# controller.net
KiCad netlist of a schematic drawn in EAGLE
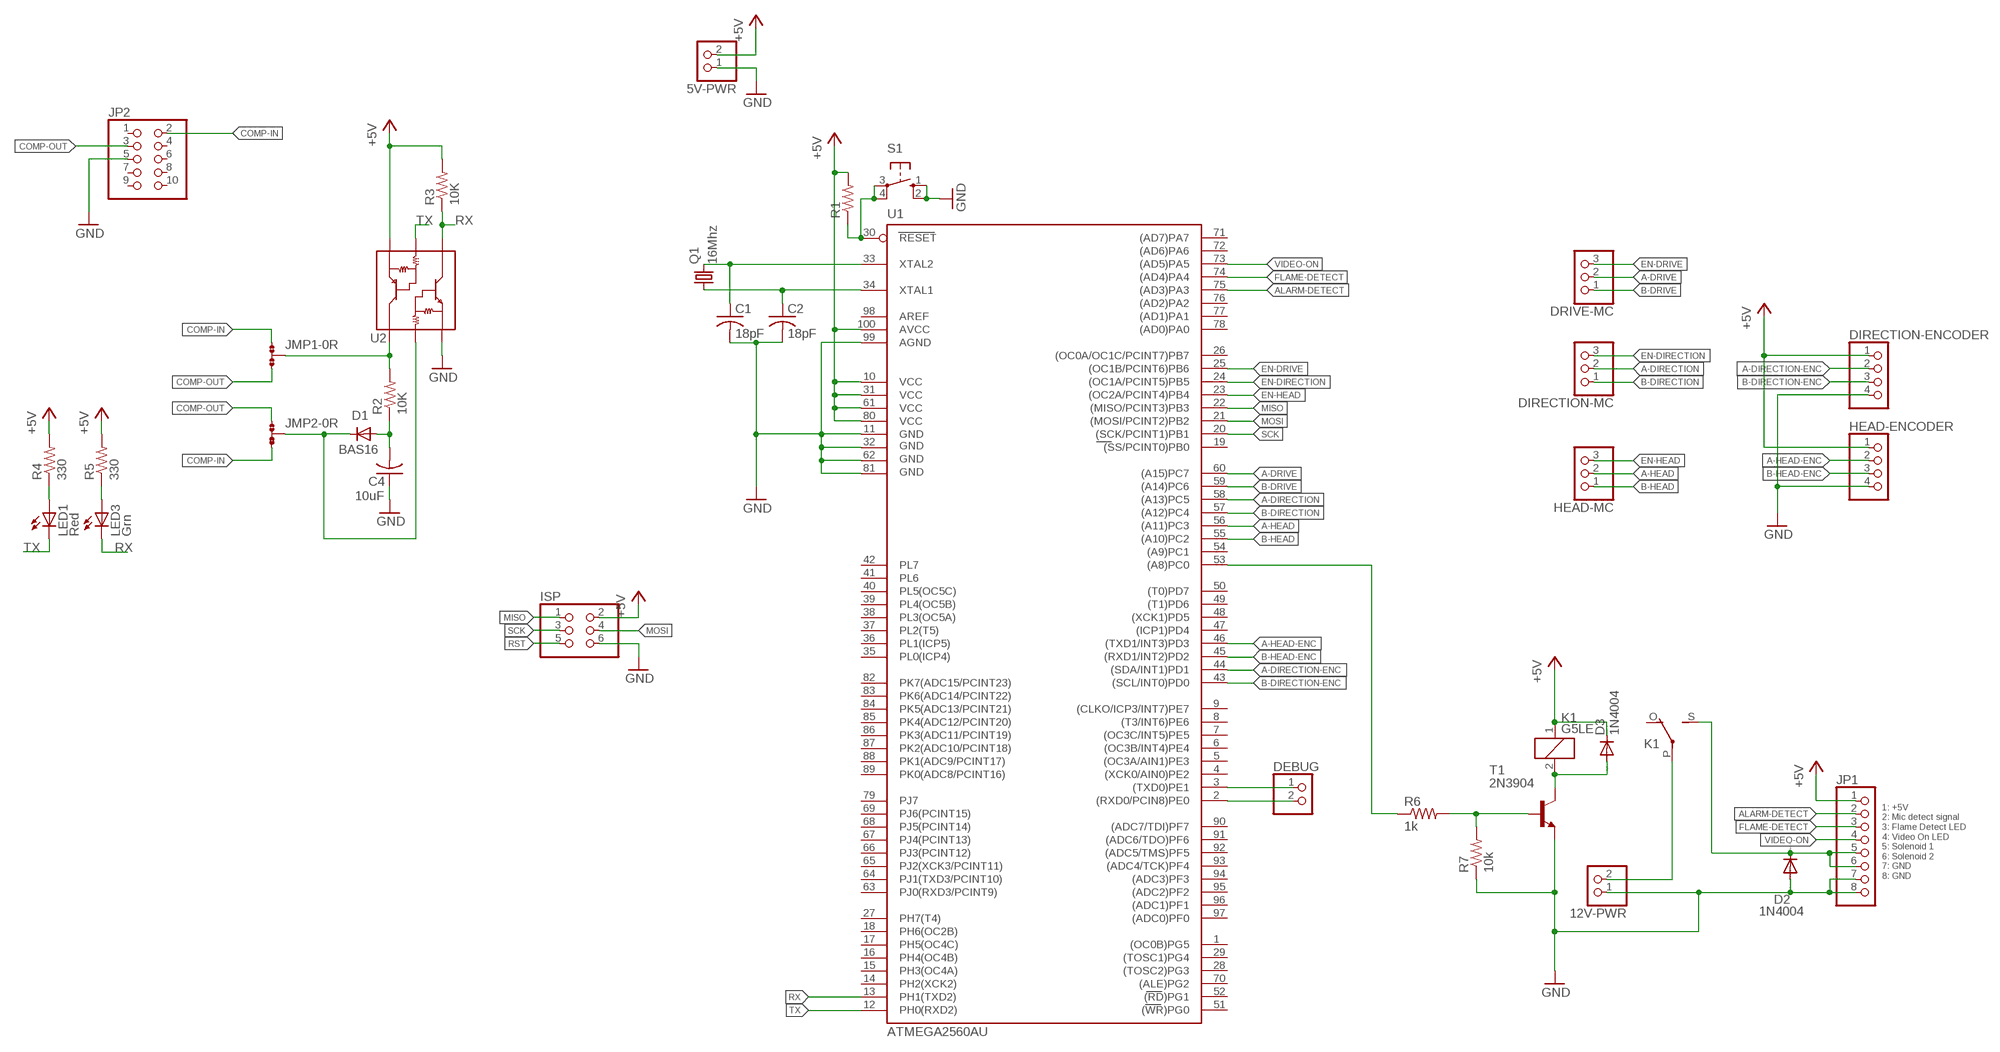
[diagram p0: schematic, sheet 1]

(export (version "E")
  (design (tool "Eeschema 10.0.6"))
  (components
    (comp (ref "5V-PWR")
      (value "PINHD-1X2")
      (footprint "eagle-import:1X02")
      (libsource (lib "eagle-import") (part "PINHD-1X2"))
    )
    (comp (ref "12V-PWR")
      (value "PINHD-1X2")
      (footprint "eagle-import:1X02")
      (libsource (lib "eagle-import") (part "PINHD-1X2"))
    )
    (comp (ref "C1")
      (value "18pF")
      (footprint "eagle-import:C0402K")
      (libsource (lib "eagle-import") (part "C-USC0402K"))
    )
    (comp (ref "C2")
      (value "18pF")
      (footprint "eagle-import:C0402K")
      (libsource (lib "eagle-import") (part "C-USC0402K"))
    )
    (comp (ref "C4")
      (value "10uF")
      (footprint "eagle-import:C0805")
      (libsource (lib "eagle-import") (part "resistor_C-USC0805"))
    )
    (comp (ref "D1")
      (value "BAS16")
      (footprint "eagle-import:SOD-323")
      (libsource (lib "eagle-import") (part "DIODESOD"))
    )
    (comp (ref "D2")
      (value "1N4004")
      (footprint "eagle-import:DO41-10")
      (libsource (lib "eagle-import") (part "1N4004"))
    )
    (comp (ref "D3")
      (value "1N4004")
      (footprint "eagle-import:DO41-10")
      (libsource (lib "eagle-import") (part "1N4004"))
    )
    (comp (ref "DEBUG")
      (value "PINHD-1X2")
      (footprint "eagle-import:1X02")
      (libsource (lib "eagle-import") (part "PINHD-1X2"))
    )
    (comp (ref "DIRECTION-ENCODER")
      (value "PINHD-1X4")
      (footprint "eagle-import:1X04")
      (libsource (lib "eagle-import") (part "PINHD-1X4"))
    )
    (comp (ref "DIRECTION-MC")
      (value "PINHD-1X3")
      (footprint "eagle-import:1X03")
      (libsource (lib "eagle-import") (part "PINHD-1X3"))
    )
    (comp (ref "DRIVE-MC")
      (value "PINHD-1X3")
      (footprint "eagle-import:1X03")
      (libsource (lib "eagle-import") (part "PINHD-1X3"))
    )
    (comp (ref "HEAD-ENCODER")
      (value "PINHD-1X4")
      (footprint "eagle-import:1X04")
      (libsource (lib "eagle-import") (part "PINHD-1X4"))
    )
    (comp (ref "HEAD-MC")
      (value "PINHD-1X3")
      (footprint "eagle-import:1X03")
      (libsource (lib "eagle-import") (part "PINHD-1X3"))
    )
    (comp (ref "ISP")
      (value "PINHD-2X3")
      (footprint "eagle-import:2X03")
      (libsource (lib "eagle-import") (part "PINHD-2X3"))
    )
    (comp (ref "JMP1")
      (value "0R-JUMPA")
      (footprint "eagle-import:A0R-JMP")
      (libsource (lib "eagle-import") (part "0R-JUMPA"))
    )
    (comp (ref "JMP2")
      (value "0R-JUMPA")
      (footprint "eagle-import:A0R-JMP")
      (libsource (lib "eagle-import") (part "0R-JUMPA"))
    )
    (comp (ref "JP1")
      (value "PINHD-1X8")
      (footprint "eagle-import:1X08")
      (libsource (lib "eagle-import") (part "PINHD-1X8"))
    )
    (comp (ref "JP2")
      (value "PINHD-2X5")
      (footprint "eagle-import:2X05")
      (libsource (lib "eagle-import") (part "PINHD-2X5"))
    )
    (comp (ref "K1")
      (value "G5LE")
      (footprint "eagle-import:G5LE")
      (libsource (lib "eagle-import") (part "G5LE"))
    )
    (comp (ref "LED1")
      (value "Red")
      (footprint "eagle-import:LED-1206")
      (libsource (lib "eagle-import") (part "LED1206"))
    )
    (comp (ref "LED3")
      (value "Grn")
      (footprint "eagle-import:LED-1206")
      (libsource (lib "eagle-import") (part "LED1206"))
    )
    (comp (ref "Q1")
      (value "16Mhz")
      (footprint "eagle-import:HC49_S")
      (libsource (lib "eagle-import") (part "CRYSTALHC49S"))
    )
    (comp (ref "R1")
      (value "R-US_M0805")
      (footprint "eagle-import:M0805")
      (libsource (lib "eagle-import") (part "R-US_M0805"))
    )
    (comp (ref "R2")
      (value "10K")
      (footprint "eagle-import:R0805")
      (libsource (lib "eagle-import") (part "resistor_R-US_R0805"))
    )
    (comp (ref "R3")
      (value "10K")
      (footprint "eagle-import:R0805")
      (libsource (lib "eagle-import") (part "resistor_R-US_R0805"))
    )
    (comp (ref "R4")
      (value "330")
      (footprint "eagle-import:R0805")
      (libsource (lib "eagle-import") (part "resistor_R-US_R0805"))
    )
    (comp (ref "R5")
      (value "330")
      (footprint "eagle-import:R0805")
      (libsource (lib "eagle-import") (part "resistor_R-US_R0805"))
    )
    (comp (ref "R6")
      (value "1k")
      (footprint "eagle-import:R0805")
      (libsource (lib "eagle-import") (part "R-US_R0805"))
    )
    (comp (ref "R7")
      (value "10k")
      (footprint "eagle-import:R0805")
      (libsource (lib "eagle-import") (part "R-US_R0805"))
    )
    (comp (ref "S1")
      (value "10-XX")
      (footprint "eagle-import:B3F-10XX")
      (fields (field (name "MPN") "B3F-1000"))
      (libsource (lib "eagle-import") (part "10-XX"))
    )
    (comp (ref "T1")
      (value "2N3904")
      (footprint "eagle-import:TO92")
      (libsource (lib "eagle-import") (part "2N3904"))
    )
    (comp (ref "U1")
      (value "ATMEGA2560AU")
      (footprint "eagle-import:TQFP100")
      (libsource (lib "eagle-import") (part "ATMEGA2560AU"))
    )
    (comp (ref "U2")
      (value "XN04312")
      (footprint "eagle-import:SOT23-6")
      (libsource (lib "eagle-import") (part "XN04312SOT"))
    )
  )
  (nets
    (net (code "1") (name "+5V") (class "Default")
      (node (ref "5V-PWR") (pin "2") (pinfunction "2_2") (pintype "passive"))
      (node (ref "D3") (pin "C") (pinfunction "C_C") (pintype "passive"))
      (node (ref "DIRECTION-ENCODER") (pin "1") (pinfunction "1_1") (pintype "passive"))
      (node (ref "HEAD-ENCODER") (pin "1") (pinfunction "1_1") (pintype "passive"))
      (node (ref "ISP") (pin "2") (pinfunction "2_2") (pintype "passive"))
      (node (ref "JP1") (pin "1") (pinfunction "1_1") (pintype "passive"))
      (node (ref "K1") (pin "1") (pinfunction "1_1") (pintype "passive"))
      (node (ref "R1") (pin "2") (pinfunction "2_2") (pintype "passive"))
      (node (ref "R3") (pin "2") (pinfunction "2_2") (pintype "passive"))
      (node (ref "R4") (pin "2") (pinfunction "2_2") (pintype "passive"))
      (node (ref "R5") (pin "2") (pinfunction "2_2") (pintype "passive"))
      (node (ref "U1") (pin "10") (pinfunction "VCC_10") (pintype "power_in"))
      (node (ref "U1") (pin "100") (pinfunction "AVCC_100") (pintype "power_in"))
      (node (ref "U1") (pin "31") (pinfunction "VCC1_31") (pintype "power_in"))
      (node (ref "U1") (pin "61") (pinfunction "VCC2_61") (pintype "power_in"))
      (node (ref "U1") (pin "80") (pinfunction "VCC3_80") (pintype "power_in"))
      (node (ref "U2") (pin "3") (pinfunction "E2_3") (pintype "bidirectional"))
    )
    (net (code "2") (name "A-DIRECTION") (class "Default")
      (node (ref "DIRECTION-MC") (pin "2") (pinfunction "2_2") (pintype "passive"))
      (node (ref "U1") (pin "58") (pinfunction "(A13)PC5_58") (pintype "bidirectional"))
    )
    (net (code "3") (name "A-DIRECTION-ENC") (class "Default")
      (node (ref "DIRECTION-ENCODER") (pin "2") (pinfunction "2_2") (pintype "passive"))
      (node (ref "U1") (pin "44") (pinfunction "(SDA/INT1)PD1_44") (pintype "bidirectional"))
    )
    (net (code "4") (name "A-DRIVE") (class "Default")
      (node (ref "DRIVE-MC") (pin "2") (pinfunction "2_2") (pintype "passive"))
      (node (ref "U1") (pin "60") (pinfunction "(A15)PC7_60") (pintype "bidirectional"))
    )
    (net (code "5") (name "A-HEAD") (class "Default")
      (node (ref "HEAD-MC") (pin "2") (pinfunction "2_2") (pintype "passive"))
      (node (ref "U1") (pin "56") (pinfunction "(A11)PC3_56") (pintype "bidirectional"))
    )
    (net (code "6") (name "A-HEAD-ENC") (class "Default")
      (node (ref "HEAD-ENCODER") (pin "2") (pinfunction "2_2") (pintype "passive"))
      (node (ref "U1") (pin "46") (pinfunction "(TXD1/INT3)PD3_46") (pintype "bidirectional"))
    )
    (net (code "7") (name "ALARM-DETECT") (class "Default")
      (node (ref "JP1") (pin "2") (pinfunction "2_2") (pintype "passive"))
      (node (ref "U1") (pin "75") (pinfunction "(AD3)PA3_75") (pintype "bidirectional"))
    )
    (net (code "8") (name "B-DIRECTION") (class "Default")
      (node (ref "DIRECTION-MC") (pin "1") (pinfunction "1_1") (pintype "passive"))
      (node (ref "U1") (pin "57") (pinfunction "(A12)PC4_57") (pintype "bidirectional"))
    )
    (net (code "9") (name "B-DIRECTION-ENC") (class "Default")
      (node (ref "DIRECTION-ENCODER") (pin "3") (pinfunction "3_3") (pintype "passive"))
      (node (ref "U1") (pin "43") (pinfunction "(SCL/INT0)PD0_43") (pintype "bidirectional"))
    )
    (net (code "10") (name "B-DRIVE") (class "Default")
      (node (ref "DRIVE-MC") (pin "1") (pinfunction "1_1") (pintype "passive"))
      (node (ref "U1") (pin "59") (pinfunction "(A14)PC6_59") (pintype "bidirectional"))
    )
    (net (code "11") (name "B-HEAD") (class "Default")
      (node (ref "HEAD-MC") (pin "1") (pinfunction "1_1") (pintype "passive"))
      (node (ref "U1") (pin "55") (pinfunction "(A10)PC2_55") (pintype "bidirectional"))
    )
    (net (code "12") (name "B-HEAD-ENC") (class "Default")
      (node (ref "HEAD-ENCODER") (pin "3") (pinfunction "3_3") (pintype "passive"))
      (node (ref "U1") (pin "45") (pinfunction "(RXD1/INT2)PD2_45") (pintype "bidirectional"))
    )
    (net (code "13") (name "COMP-IN") (class "Default")
      (node (ref "JMP1") (pin "1") (pinfunction "1_1") (pintype "passive"))
      (node (ref "JMP2") (pin "3") (pinfunction "3_3") (pintype "passive"))
      (node (ref "JP2") (pin "2") (pinfunction "2_2") (pintype "passive"))
    )
    (net (code "14") (name "COMP-OUT") (class "Default")
      (node (ref "JMP1") (pin "3") (pinfunction "3_3") (pintype "passive"))
      (node (ref "JMP2") (pin "1") (pinfunction "1_1") (pintype "passive"))
      (node (ref "JP2") (pin "3") (pinfunction "3_3") (pintype "passive"))
    )
    (net (code "15") (name "EN-DIRECTION") (class "Default")
      (node (ref "DIRECTION-MC") (pin "3") (pinfunction "3_3") (pintype "passive"))
      (node (ref "U1") (pin "24") (pinfunction "(OC1A/PCINT5)PB5_24") (pintype "bidirectional"))
    )
    (net (code "16") (name "EN-DRIVE") (class "Default")
      (node (ref "DRIVE-MC") (pin "3") (pinfunction "3_3") (pintype "passive"))
      (node (ref "U1") (pin "25") (pinfunction "(OC1B/PCINT6)PB6_25") (pintype "bidirectional"))
    )
    (net (code "17") (name "EN-HEAD") (class "Default")
      (node (ref "HEAD-MC") (pin "3") (pinfunction "3_3") (pintype "passive"))
      (node (ref "U1") (pin "23") (pinfunction "(OC2A/PCINT4)PB4_23") (pintype "bidirectional"))
    )
    (net (code "18") (name "FLAME-DETECT") (class "Default")
      (node (ref "JP1") (pin "3") (pinfunction "3_3") (pintype "passive"))
      (node (ref "U1") (pin "74") (pinfunction "(AD4)PA4_74") (pintype "bidirectional"))
    )
    (net (code "19") (name "GND") (class "Default")
      (node (ref "12V-PWR") (pin "1") (pinfunction "1_1") (pintype "passive"))
      (node (ref "5V-PWR") (pin "1") (pinfunction "1_1") (pintype "passive"))
      (node (ref "C1") (pin "2") (pinfunction "2_2") (pintype "passive"))
      (node (ref "C2") (pin "2") (pinfunction "2_2") (pintype "passive"))
      (node (ref "C4") (pin "1") (pinfunction "1_1") (pintype "passive"))
      (node (ref "D2") (pin "A") (pinfunction "A_A") (pintype "passive"))
      (node (ref "DIRECTION-ENCODER") (pin "4") (pinfunction "4_4") (pintype "passive"))
      (node (ref "HEAD-ENCODER") (pin "4") (pinfunction "4_4") (pintype "passive"))
      (node (ref "ISP") (pin "6") (pinfunction "6_6") (pintype "passive"))
      (node (ref "JP1") (pin "7") (pinfunction "7_7") (pintype "passive"))
      (node (ref "JP1") (pin "8") (pinfunction "8_8") (pintype "passive"))
      (node (ref "JP2") (pin "5") (pinfunction "5_5") (pintype "passive"))
      (node (ref "R7") (pin "1") (pinfunction "1_1") (pintype "passive"))
      (node (ref "S1") (pin "1") (pinfunction "S_1") (pintype "passive"))
      (node (ref "S1") (pin "2") (pinfunction "S1_2") (pintype "passive"))
      (node (ref "T1") (pin "3") (pinfunction "E_3") (pintype "passive"))
      (node (ref "U1") (pin "11") (pinfunction "GND_11") (pintype "power_in"))
      (node (ref "U1") (pin "32") (pinfunction "GND1_32") (pintype "power_in"))
      (node (ref "U1") (pin "62") (pinfunction "GND2_62") (pintype "power_in"))
      (node (ref "U1") (pin "81") (pinfunction "GND3_81") (pintype "power_in"))
      (node (ref "U1") (pin "99") (pinfunction "AGND_99") (pintype "power_in"))
      (node (ref "U2") (pin "6") (pinfunction "E1_6") (pintype "bidirectional"))
    )
    (net (code "20") (name "MISO") (class "Default")
      (node (ref "ISP") (pin "1") (pinfunction "1_1") (pintype "passive"))
      (node (ref "U1") (pin "22") (pinfunction "(MISO/PCINT3)PB3_22") (pintype "bidirectional"))
    )
    (net (code "21") (name "MOSI") (class "Default")
      (node (ref "ISP") (pin "4") (pinfunction "4_4") (pintype "passive"))
      (node (ref "U1") (pin "21") (pinfunction "(MOSI/PCINT2)PB2_21") (pintype "bidirectional"))
    )
    (net (code "22") (name "Net-(12V-PWR-Pad2)") (class "Default")
      (node (ref "12V-PWR") (pin "2") (pinfunction "2_2") (pintype "passive"))
      (node (ref "K1") (pin "P") (pinfunction "P_P") (pintype "passive"))
    )
    (net (code "23") (name "Net-(D1-A)") (class "Default")
      (node (ref "C4") (pin "2") (pinfunction "2_2") (pintype "passive"))
      (node (ref "D1") (pin "2") (pinfunction "A_2") (pintype "passive"))
      (node (ref "R2") (pin "1") (pinfunction "1_1") (pintype "passive"))
    )
    (net (code "24") (name "Net-(D1-C)") (class "Default")
      (node (ref "D1") (pin "1") (pinfunction "C_1") (pintype "passive"))
      (node (ref "JMP2") (pin "2") (pinfunction "2_2") (pintype "passive"))
      (node (ref "U2") (pin "5") (pinfunction "B1_5") (pintype "bidirectional"))
    )
    (net (code "25") (name "Net-(D2-PadC)") (class "Default")
      (node (ref "D2") (pin "C") (pinfunction "C_C") (pintype "passive"))
      (node (ref "JP1") (pin "5") (pinfunction "5_5") (pintype "passive"))
      (node (ref "JP1") (pin "6") (pinfunction "6_6") (pintype "passive"))
      (node (ref "K1") (pin "S") (pinfunction "S_S") (pintype "passive"))
    )
    (net (code "26") (name "Net-(LED1-PadA)") (class "Default")
      (node (ref "LED1") (pin "A") (pinfunction "A_A") (pintype "passive"))
      (node (ref "R4") (pin "1") (pinfunction "1_1") (pintype "passive"))
    )
    (net (code "27") (name "Net-(LED3-PadA)") (class "Default")
      (node (ref "LED3") (pin "A") (pinfunction "A_A") (pintype "passive"))
      (node (ref "R5") (pin "1") (pinfunction "1_1") (pintype "passive"))
    )
    (net (code "28") (name "Net-(T1-B)") (class "Default")
      (node (ref "R6") (pin "2") (pinfunction "2_2") (pintype "passive"))
      (node (ref "R7") (pin "2") (pinfunction "2_2") (pintype "passive"))
      (node (ref "T1") (pin "2") (pinfunction "B_2") (pintype "passive"))
    )
    (net (code "29") (name "Net-(T1-C)") (class "Default")
      (node (ref "D3") (pin "A") (pinfunction "A_A") (pintype "passive"))
      (node (ref "K1") (pin "2") (pinfunction "2_2") (pintype "passive"))
      (node (ref "T1") (pin "1") (pinfunction "C_1") (pintype "passive"))
    )
    (net (code "30") (name "Net-(U1-(A8)PC0)") (class "Default")
      (node (ref "R6") (pin "1") (pinfunction "1_1") (pintype "passive"))
      (node (ref "U1") (pin "53") (pinfunction "(A8)PC0_53") (pintype "bidirectional"))
    )
    (net (code "31") (name "Net-(U1-(RXD0{slash}PCIN8)PE0)") (class "Default")
      (node (ref "DEBUG") (pin "2") (pinfunction "2_2") (pintype "passive"))
      (node (ref "U1") (pin "2") (pinfunction "(RXD0/PCIN8)PE0_2") (pintype "bidirectional"))
    )
    (net (code "32") (name "Net-(U1-(TXD0)PE1)") (class "Default")
      (node (ref "DEBUG") (pin "1") (pinfunction "1_1") (pintype "passive"))
      (node (ref "U1") (pin "3") (pinfunction "(TXD0)PE1_3") (pintype "bidirectional"))
    )
    (net (code "33") (name "Net-(U1-XTAL1)") (class "Default")
      (node (ref "C2") (pin "1") (pinfunction "1_1") (pintype "passive"))
      (node (ref "Q1") (pin "1") (pinfunction "1_1") (pintype "passive"))
      (node (ref "U1") (pin "34") (pinfunction "XTAL1_34") (pintype "input"))
    )
    (net (code "34") (name "Net-(U1-XTAL2)") (class "Default")
      (node (ref "C1") (pin "1") (pinfunction "1_1") (pintype "passive"))
      (node (ref "Q1") (pin "2") (pinfunction "2_2") (pintype "passive"))
      (node (ref "U1") (pin "33") (pinfunction "XTAL2_33") (pintype "output"))
    )
    (net (code "35") (name "Net-(U2-C2)") (class "Default")
      (node (ref "JMP1") (pin "2") (pinfunction "2_2") (pintype "passive"))
      (node (ref "R2") (pin "2") (pinfunction "2_2") (pintype "passive"))
      (node (ref "U2") (pin "4") (pinfunction "C2_4") (pintype "bidirectional"))
    )
    (net (code "36") (name "RST") (class "Default")
      (node (ref "ISP") (pin "5") (pinfunction "5_5") (pintype "passive"))
      (node (ref "R1") (pin "1") (pinfunction "1_1") (pintype "passive"))
      (node (ref "S1") (pin "3") (pinfunction "P_3") (pintype "passive"))
      (node (ref "S1") (pin "4") (pinfunction "P1_4") (pintype "passive"))
      (node (ref "U1") (pin "30") (pinfunction "RESET_30") (pintype "input"))
    )
    (net (code "37") (name "RX") (class "Default")
      (node (ref "LED3") (pin "C") (pinfunction "C_C") (pintype "passive"))
      (node (ref "R3") (pin "1") (pinfunction "1_1") (pintype "passive"))
      (node (ref "U1") (pin "13") (pinfunction "PH1(TXD2)_13") (pintype "bidirectional"))
      (node (ref "U2") (pin "1") (pinfunction "C1_1") (pintype "bidirectional"))
    )
    (net (code "38") (name "SCK") (class "Default")
      (node (ref "ISP") (pin "3") (pinfunction "3_3") (pintype "passive"))
      (node (ref "U1") (pin "20") (pinfunction "(SCK/PCINT1)PB1_20") (pintype "bidirectional"))
    )
    (net (code "39") (name "TX") (class "Default")
      (node (ref "LED1") (pin "C") (pinfunction "C_C") (pintype "passive"))
      (node (ref "U1") (pin "12") (pinfunction "PH0(RXD2)_12") (pintype "bidirectional"))
      (node (ref "U2") (pin "2") (pinfunction "B2_2") (pintype "bidirectional"))
    )
    (net (code "40") (name "VIDEO-ON") (class "Default")
      (node (ref "JP1") (pin "4") (pinfunction "4_4") (pintype "passive"))
      (node (ref "U1") (pin "73") (pinfunction "(AD5)PA5_73") (pintype "bidirectional"))
    )
    (net (code "41") (name "unconnected-(JP2-Pad1)") (class "Default")
      (node (ref "JP2") (pin "1") (pinfunction "1_1") (pintype "passive"))
    )
    (net (code "42") (name "unconnected-(JP2-Pad4)") (class "Default")
      (node (ref "JP2") (pin "4") (pinfunction "4_4") (pintype "passive"))
    )
    (net (code "43") (name "unconnected-(JP2-Pad6)") (class "Default")
      (node (ref "JP2") (pin "6") (pinfunction "6_6") (pintype "passive"))
    )
    (net (code "44") (name "unconnected-(JP2-Pad7)") (class "Default")
      (node (ref "JP2") (pin "7") (pinfunction "7_7") (pintype "passive"))
    )
    (net (code "45") (name "unconnected-(JP2-Pad8)") (class "Default")
      (node (ref "JP2") (pin "8") (pinfunction "8_8") (pintype "passive"))
    )
    (net (code "46") (name "unconnected-(JP2-Pad9)") (class "Default")
      (node (ref "JP2") (pin "9") (pinfunction "9_9") (pintype "passive"))
    )
    (net (code "47") (name "unconnected-(JP2-Pad10)") (class "Default")
      (node (ref "JP2") (pin "10") (pinfunction "10_10") (pintype "passive"))
    )
    (net (code "48") (name "unconnected-(K1-PadO)") (class "Default")
      (node (ref "K1") (pin "O") (pinfunction "O_O") (pintype "passive"))
    )
    (net (code "49") (name "unconnected-(U1-(A9)PC1-Pad54)") (class "Default")
      (node (ref "U1") (pin "54") (pinfunction "(A9)PC1_54") (pintype "bidirectional"))
    )
    (net (code "50") (name "unconnected-(U1-(AD0)PA0-Pad78)") (class "Default")
      (node (ref "U1") (pin "78") (pinfunction "(AD0)PA0_78") (pintype "bidirectional"))
    )
    (net (code "51") (name "unconnected-(U1-(AD1)PA1-Pad77)") (class "Default")
      (node (ref "U1") (pin "77") (pinfunction "(AD1)PA1_77") (pintype "bidirectional"))
    )
    (net (code "52") (name "unconnected-(U1-(AD2)PA2-Pad76)") (class "Default")
      (node (ref "U1") (pin "76") (pinfunction "(AD2)PA2_76") (pintype "bidirectional"))
    )
    (net (code "53") (name "unconnected-(U1-(AD6)PA6-Pad72)") (class "Default")
      (node (ref "U1") (pin "72") (pinfunction "(AD6)PA6_72") (pintype "bidirectional"))
    )
    (net (code "54") (name "unconnected-(U1-(AD7)PA7-Pad71)") (class "Default")
      (node (ref "U1") (pin "71") (pinfunction "(AD7)PA7_71") (pintype "bidirectional"))
    )
    (net (code "55") (name "unconnected-(U1-(ADC0)PF0-Pad97)") (class "Default")
      (node (ref "U1") (pin "97") (pinfunction "(ADC0)PF0_97") (pintype "bidirectional"))
    )
    (net (code "56") (name "unconnected-(U1-(ADC1)PF1-Pad96)") (class "Default")
      (node (ref "U1") (pin "96") (pinfunction "(ADC1)PF1_96") (pintype "bidirectional"))
    )
    (net (code "57") (name "unconnected-(U1-(ADC2)PF2-Pad95)") (class "Default")
      (node (ref "U1") (pin "95") (pinfunction "(ADC2)PF2_95") (pintype "bidirectional"))
    )
    (net (code "58") (name "unconnected-(U1-(ADC3)PF3-Pad94)") (class "Default")
      (node (ref "U1") (pin "94") (pinfunction "(ADC3)PF3_94") (pintype "bidirectional"))
    )
    (net (code "59") (name "unconnected-(U1-(ADC4{slash}TCK)PF4-Pad93)") (class "Default")
      (node (ref "U1") (pin "93") (pinfunction "(ADC4/TCK)PF4_93") (pintype "bidirectional"))
    )
    (net (code "60") (name "unconnected-(U1-(ADC5{slash}TMS)PF5-Pad92)") (class "Default")
      (node (ref "U1") (pin "92") (pinfunction "(ADC5/TMS)PF5_92") (pintype "bidirectional"))
    )
    (net (code "61") (name "unconnected-(U1-(ADC6{slash}TDO)PF6-Pad91)") (class "Default")
      (node (ref "U1") (pin "91") (pinfunction "(ADC6/TDO)PF6_91") (pintype "bidirectional"))
    )
    (net (code "62") (name "unconnected-(U1-(ADC7{slash}TDI)PF7-Pad90)") (class "Default")
      (node (ref "U1") (pin "90") (pinfunction "(ADC7/TDI)PF7_90") (pintype "bidirectional"))
    )
    (net (code "63") (name "unconnected-(U1-(ALE)PG2-Pad70)") (class "Default")
      (node (ref "U1") (pin "70") (pinfunction "(ALE)PG2_70") (pintype "bidirectional"))
    )
    (net (code "64") (name "unconnected-(U1-(CLKO{slash}ICP3{slash}INT7)PE7-Pad9)") (class "Default")
      (node (ref "U1") (pin "9") (pinfunction "(CLKO/ICP3/INT7)PE7_9") (pintype "bidirectional"))
    )
    (net (code "65") (name "unconnected-(U1-(ICP1)PD4-Pad47)") (class "Default")
      (node (ref "U1") (pin "47") (pinfunction "(ICP1)PD4_47") (pintype "bidirectional"))
    )
    (net (code "66") (name "unconnected-(U1-(OC0A{slash}OC1C{slash}PCINT7)PB7-Pad26)") (class "Default")
      (node (ref "U1") (pin "26") (pinfunction "(OC0A/OC1C/PCINT7)PB7_26") (pintype "bidirectional"))
    )
    (net (code "67") (name "unconnected-(U1-(OC0B)PG5-Pad1)") (class "Default")
      (node (ref "U1") (pin "1") (pinfunction "(OC0B)PG5_1") (pintype "bidirectional"))
    )
    (net (code "68") (name "unconnected-(U1-(OC3A{slash}AIN1)PE3-Pad5)") (class "Default")
      (node (ref "U1") (pin "5") (pinfunction "(OC3A/AIN1)PE3_5") (pintype "bidirectional"))
    )
    (net (code "69") (name "unconnected-(U1-(OC3B{slash}INT4)PE4-Pad6)") (class "Default")
      (node (ref "U1") (pin "6") (pinfunction "(OC3B/INT4)PE4_6") (pintype "bidirectional"))
    )
    (net (code "70") (name "unconnected-(U1-(OC3C{slash}INT5)PE5-Pad7)") (class "Default")
      (node (ref "U1") (pin "7") (pinfunction "(OC3C/INT5)PE5_7") (pintype "bidirectional"))
    )
    (net (code "71") (name "unconnected-(U1-(RD)PG1-Pad52)") (class "Default")
      (node (ref "U1") (pin "52") (pinfunction "(RD)PG1_52") (pintype "bidirectional"))
    )
    (net (code "72") (name "unconnected-(U1-(SS{slash}PCINT0)PB0-Pad19)") (class "Default")
      (node (ref "U1") (pin "19") (pinfunction "(SS/PCINT0)PB0_19") (pintype "bidirectional"))
    )
    (net (code "73") (name "unconnected-(U1-(T0)PD7-Pad50)") (class "Default")
      (node (ref "U1") (pin "50") (pinfunction "(T0)PD7_50") (pintype "bidirectional"))
    )
    (net (code "74") (name "unconnected-(U1-(T1)PD6-Pad49)") (class "Default")
      (node (ref "U1") (pin "49") (pinfunction "(T1)PD6_49") (pintype "bidirectional"))
    )
    (net (code "75") (name "unconnected-(U1-(T3{slash}INT6)PE6-Pad8)") (class "Default")
      (node (ref "U1") (pin "8") (pinfunction "(T3/INT6)PE6_8") (pintype "bidirectional"))
    )
    (net (code "76") (name "unconnected-(U1-(TOSC1)PG4-Pad29)") (class "Default")
      (node (ref "U1") (pin "29") (pinfunction "(TOSC1)PG4_29") (pintype "bidirectional"))
    )
    (net (code "77") (name "unconnected-(U1-(TOSC2)PG3-Pad28)") (class "Default")
      (node (ref "U1") (pin "28") (pinfunction "(TOSC2)PG3_28") (pintype "bidirectional"))
    )
    (net (code "78") (name "unconnected-(U1-(WR)PG0-Pad51)") (class "Default")
      (node (ref "U1") (pin "51") (pinfunction "(WR)PG0_51") (pintype "bidirectional"))
    )
    (net (code "79") (name "unconnected-(U1-(XCK0{slash}AIN0)PE2-Pad4)") (class "Default")
      (node (ref "U1") (pin "4") (pinfunction "(XCK0/AIN0)PE2_4") (pintype "bidirectional"))
    )
    (net (code "80") (name "unconnected-(U1-(XCK1)PD5-Pad48)") (class "Default")
      (node (ref "U1") (pin "48") (pinfunction "(XCK1)PD5_48") (pintype "bidirectional"))
    )
    (net (code "81") (name "unconnected-(U1-AREF-Pad98)") (class "Default")
      (node (ref "U1") (pin "98") (pinfunction "AREF_98") (pintype "bidirectional"))
    )
    (net (code "82") (name "unconnected-(U1-PH2(XCK2)-Pad14)") (class "Default")
      (node (ref "U1") (pin "14") (pinfunction "PH2(XCK2)_14") (pintype "bidirectional"))
    )
    (net (code "83") (name "unconnected-(U1-PH3(OC4A)-Pad15)") (class "Default")
      (node (ref "U1") (pin "15") (pinfunction "PH3(OC4A)_15") (pintype "bidirectional"))
    )
    (net (code "84") (name "unconnected-(U1-PH4(OC4B)-Pad16)") (class "Default")
      (node (ref "U1") (pin "16") (pinfunction "PH4(OC4B)_16") (pintype "bidirectional"))
    )
    (net (code "85") (name "unconnected-(U1-PH5(OC4C)-Pad17)") (class "Default")
      (node (ref "U1") (pin "17") (pinfunction "PH5(OC4C)_17") (pintype "bidirectional"))
    )
    (net (code "86") (name "unconnected-(U1-PH6(OC2B)-Pad18)") (class "Default")
      (node (ref "U1") (pin "18") (pinfunction "PH6(OC2B)_18") (pintype "bidirectional"))
    )
    (net (code "87") (name "unconnected-(U1-PH7(T4)-Pad27)") (class "Default")
      (node (ref "U1") (pin "27") (pinfunction "PH7(T4)_27") (pintype "bidirectional"))
    )
    (net (code "88") (name "unconnected-(U1-PJ0(RXD3{slash}PCINT9)-Pad63)") (class "Default")
      (node (ref "U1") (pin "63") (pinfunction "PJ0(RXD3/PCINT9)_63") (pintype "bidirectional"))
    )
    (net (code "89") (name "unconnected-(U1-PJ1(TXD3{slash}PCINT10)-Pad64)") (class "Default")
      (node (ref "U1") (pin "64") (pinfunction "PJ1(TXD3/PCINT10)_64") (pintype "bidirectional"))
    )
    (net (code "90") (name "unconnected-(U1-PJ2(XCK3{slash}PCINT11)-Pad65)") (class "Default")
      (node (ref "U1") (pin "65") (pinfunction "PJ2(XCK3/PCINT11)_65") (pintype "bidirectional"))
    )
    (net (code "91") (name "unconnected-(U1-PJ3(PCINT12)-Pad66)") (class "Default")
      (node (ref "U1") (pin "66") (pinfunction "PJ3(PCINT12)_66") (pintype "bidirectional"))
    )
    (net (code "92") (name "unconnected-(U1-PJ4(PCINT13)-Pad67)") (class "Default")
      (node (ref "U1") (pin "67") (pinfunction "PJ4(PCINT13)_67") (pintype "bidirectional"))
    )
    (net (code "93") (name "unconnected-(U1-PJ5(PCINT14)-Pad68)") (class "Default")
      (node (ref "U1") (pin "68") (pinfunction "PJ5(PCINT14)_68") (pintype "bidirectional"))
    )
    (net (code "94") (name "unconnected-(U1-PJ6(PCINT15)-Pad69)") (class "Default")
      (node (ref "U1") (pin "69") (pinfunction "PJ6(PCINT15)_69") (pintype "bidirectional"))
    )
    (net (code "95") (name "unconnected-(U1-PJ7-Pad79)") (class "Default")
      (node (ref "U1") (pin "79") (pinfunction "PJ7_79") (pintype "bidirectional"))
    )
    (net (code "96") (name "unconnected-(U1-PK0(ADC8{slash}PCINT16)-Pad89)") (class "Default")
      (node (ref "U1") (pin "89") (pinfunction "PK0(ADC8/PCINT16)_89") (pintype "bidirectional"))
    )
    (net (code "97") (name "unconnected-(U1-PK1(ADC9{slash}PCINT17)-Pad88)") (class "Default")
      (node (ref "U1") (pin "88") (pinfunction "PK1(ADC9/PCINT17)_88") (pintype "bidirectional"))
    )
    (net (code "98") (name "unconnected-(U1-PK2(ADC10{slash}PCINT18)-Pad87)") (class "Default")
      (node (ref "U1") (pin "87") (pinfunction "PK2(ADC10/PCINT18)_87") (pintype "bidirectional"))
    )
    (net (code "99") (name "unconnected-(U1-PK3(ADC11{slash}PCINT19)-Pad86)") (class "Default")
      (node (ref "U1") (pin "86") (pinfunction "PK3(ADC11/PCINT19)_86") (pintype "bidirectional"))
    )
    (net (code "100") (name "unconnected-(U1-PK4(ADC12{slash}PCINT20)-Pad85)") (class "Default")
      (node (ref "U1") (pin "85") (pinfunction "PK4(ADC12/PCINT20)_85") (pintype "bidirectional"))
    )
    (net (code "101") (name "unconnected-(U1-PK5(ADC13{slash}PCINT21)-Pad84)") (class "Default")
      (node (ref "U1") (pin "84") (pinfunction "PK5(ADC13/PCINT21)_84") (pintype "bidirectional"))
    )
    (net (code "102") (name "unconnected-(U1-PK6(ADC14{slash}PCINT22)-Pad83)") (class "Default")
      (node (ref "U1") (pin "83") (pinfunction "PK6(ADC14/PCINT22)_83") (pintype "bidirectional"))
    )
    (net (code "103") (name "unconnected-(U1-PK7(ADC15{slash}PCINT23)-Pad82)") (class "Default")
      (node (ref "U1") (pin "82") (pinfunction "PK7(ADC15/PCINT23)_82") (pintype "bidirectional"))
    )
    (net (code "104") (name "unconnected-(U1-PL0(ICP4)-Pad35)") (class "Default")
      (node (ref "U1") (pin "35") (pinfunction "PL0(ICP4)_35") (pintype "bidirectional"))
    )
    (net (code "105") (name "unconnected-(U1-PL1(ICP5)-Pad36)") (class "Default")
      (node (ref "U1") (pin "36") (pinfunction "PL1(ICP5)_36") (pintype "bidirectional"))
    )
    (net (code "106") (name "unconnected-(U1-PL2(T5)-Pad37)") (class "Default")
      (node (ref "U1") (pin "37") (pinfunction "PL2(T5)_37") (pintype "bidirectional"))
    )
    (net (code "107") (name "unconnected-(U1-PL3(OC5A)-Pad38)") (class "Default")
      (node (ref "U1") (pin "38") (pinfunction "PL3(OC5A)_38") (pintype "bidirectional"))
    )
    (net (code "108") (name "unconnected-(U1-PL4(OC5B)-Pad39)") (class "Default")
      (node (ref "U1") (pin "39") (pinfunction "PL4(OC5B)_39") (pintype "bidirectional"))
    )
    (net (code "109") (name "unconnected-(U1-PL5(OC5C)-Pad40)") (class "Default")
      (node (ref "U1") (pin "40") (pinfunction "PL5(OC5C)_40") (pintype "bidirectional"))
    )
    (net (code "110") (name "unconnected-(U1-PL6-Pad41)") (class "Default")
      (node (ref "U1") (pin "41") (pinfunction "PL6_41") (pintype "bidirectional"))
    )
    (net (code "111") (name "unconnected-(U1-PL7-Pad42)") (class "Default")
      (node (ref "U1") (pin "42") (pinfunction "PL7_42") (pintype "bidirectional"))
    )
  )
)
